# Schematic.net
KiCad netlist of a schematic drawn in EAGLE
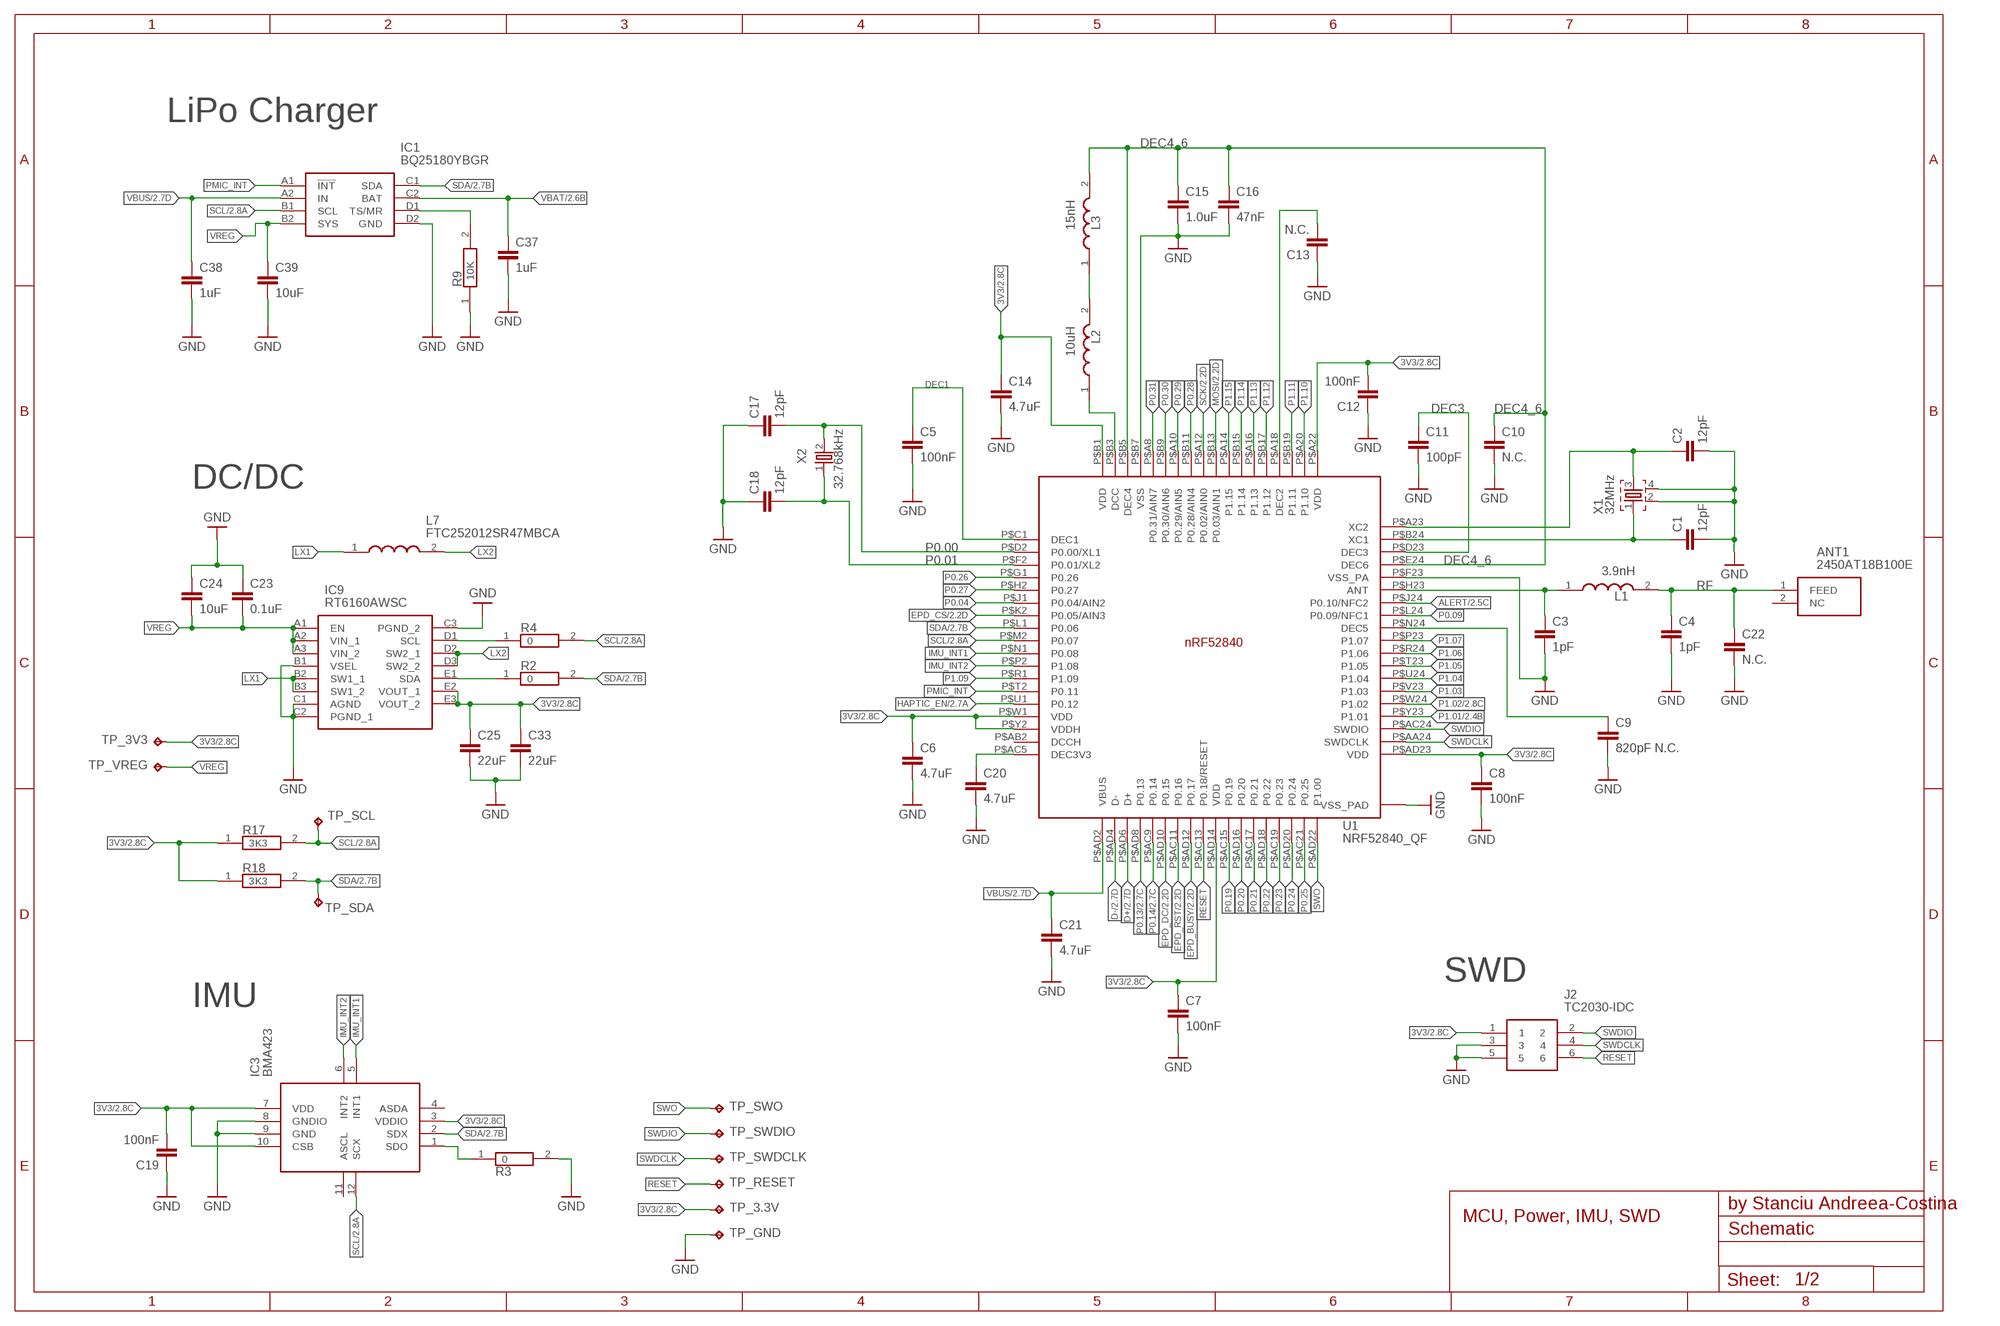
[diagram p0: schematic, sheet 1]
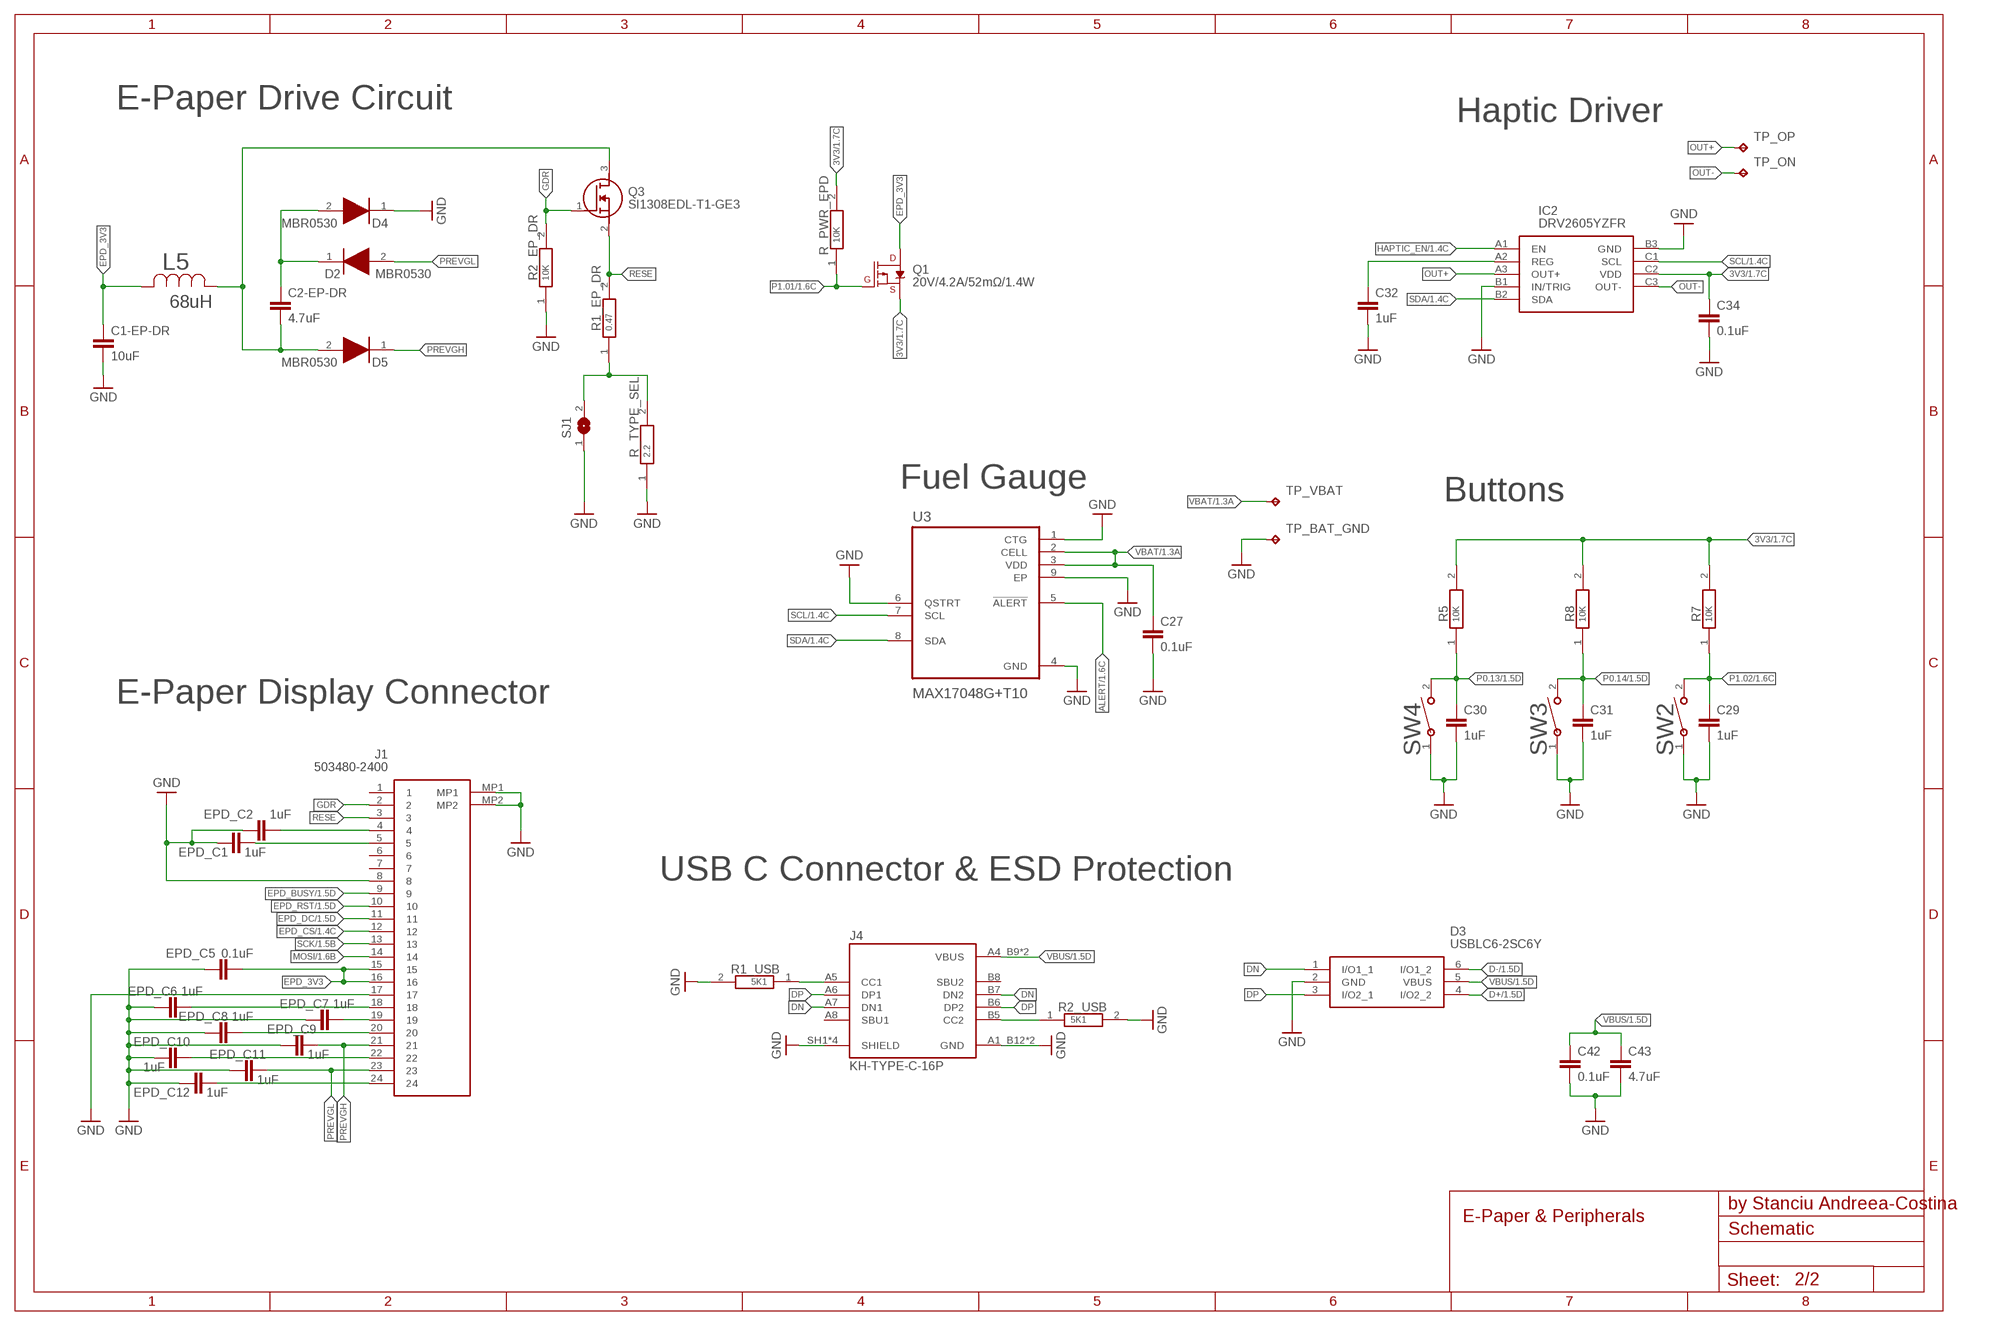
[diagram p1: schematic, sheet 2]

(export (version "E")
  (design (tool "Eeschema 10.0.6"))
  (components
    (comp (ref "ANT1")
      (value "2450AT18B100E")
      (footprint "eagle-import:2450AT18B100E_ANTC3216X140N")
      (fields (field (name "MOUSER_PART_NUMBER") "609-2450AT18B100E"))
      (libsource (lib "eagle-import") (part "2450AT18B100E_2450AT18B100E"))
    )
    (comp (ref "C1")
      (value "12pF")
      (footprint "eagle-import:NORDIC_NRF_3_RESC0201_N")
      (libsource (lib "eagle-import") (part "InkTime_v5_vf.H3x0luehSd-qGlYKXrjHOA_NORDIC_NRF_3_CAPACITOR_0201_N"))
    )
    (comp (ref "C2")
      (value "12pF")
      (footprint "eagle-import:NORDIC_NRF_3_RESC0201_N")
      (libsource (lib "eagle-import") (part "InkTime_v5_vf.H3x0luehSd-qGlYKXrjHOA_NORDIC_NRF_3_CAPACITOR_0201_N"))
    )
    (comp (ref "C3")
      (value "1pF")
      (footprint "eagle-import:NORDIC_NRF_3_RESC0201_N")
      (libsource (lib "eagle-import") (part "InkTime_v5_vf.H3x0luehSd-qGlYKXrjHOA_NORDIC_NRF_3_CAPACITOR_0201_N"))
    )
    (comp (ref "C4")
      (value "1pF")
      (footprint "eagle-import:NORDIC_NRF_3_RESC0201_N")
      (libsource (lib "eagle-import") (part "InkTime_v5_vf.H3x0luehSd-qGlYKXrjHOA_NORDIC_NRF_3_CAPACITOR_0201_N"))
    )
    (comp (ref "C5")
      (value "100nF")
      (footprint "eagle-import:NORDIC_NRF_3_RESC0201_N")
      (libsource (lib "eagle-import") (part "InkTime_v5_vf.H3x0luehSd-qGlYKXrjHOA_NORDIC_NRF_3_CAPACITOR_0201_N"))
    )
    (comp (ref "C6")
      (value "4.7uF")
      (footprint "eagle-import:NORDIC_NRF_3_RESC0402_N")
      (libsource (lib "eagle-import") (part "InkTime_v5_vf.H3x0luehSd-qGlYKXrjHOA_NORDIC_NRF_3_CAPACITOR_0402_N"))
    )
    (comp (ref "C7")
      (value "100nF")
      (footprint "eagle-import:NORDIC_NRF_3_RESC0201_N")
      (libsource (lib "eagle-import") (part "InkTime_v5_vf.H3x0luehSd-qGlYKXrjHOA_NORDIC_NRF_3_CAPACITOR_0201_N"))
    )
    (comp (ref "C8")
      (value "100nF")
      (footprint "eagle-import:NORDIC_NRF_3_RESC0201_N")
      (libsource (lib "eagle-import") (part "InkTime_v5_vf.H3x0luehSd-qGlYKXrjHOA_NORDIC_NRF_3_CAPACITOR_0201_N"))
    )
    (comp (ref "C9")
      (value "820pF N.C.")
      (footprint "eagle-import:NORDIC_NRF_3_RESC0201_N")
      (libsource (lib "eagle-import") (part "InkTime_v5_vf.H3x0luehSd-qGlYKXrjHOA_NORDIC_NRF_3_CAPACITOR_0201_N"))
    )
    (comp (ref "C10")
      (value "N.C.")
      (footprint "eagle-import:NORDIC_NRF_3_RESC0201_N")
      (libsource (lib "eagle-import") (part "InkTime_v5_vf.H3x0luehSd-qGlYKXrjHOA_NORDIC_NRF_3_CAPACITOR_0201_N"))
    )
    (comp (ref "C11")
      (value "100pF")
      (footprint "eagle-import:NORDIC_NRF_3_RESC0201_N")
      (libsource (lib "eagle-import") (part "InkTime_v5_vf.H3x0luehSd-qGlYKXrjHOA_NORDIC_NRF_3_CAPACITOR_0201_N"))
    )
    (comp (ref "C12")
      (value "100nF")
      (footprint "eagle-import:NORDIC_NRF_3_RESC0201_N")
      (libsource (lib "eagle-import") (part "InkTime_v5_vf.H3x0luehSd-qGlYKXrjHOA_NORDIC_NRF_3_CAPACITOR_0201_N"))
    )
    (comp (ref "C13")
      (value "N.C.")
      (footprint "eagle-import:NORDIC_NRF_3_RESC0201_N")
      (libsource (lib "eagle-import") (part "InkTime_v5_vf.H3x0luehSd-qGlYKXrjHOA_NORDIC_NRF_3_CAPACITOR_0201_N"))
    )
    (comp (ref "C14")
      (value "4.7uF")
      (footprint "eagle-import:NORDIC_NRF_3_RESC0402_N")
      (libsource (lib "eagle-import") (part "InkTime_v5_vf.H3x0luehSd-qGlYKXrjHOA_NORDIC_NRF_3_CAPACITOR_0402_N"))
    )
    (comp (ref "C15")
      (value "1.0uF")
      (footprint "eagle-import:NORDIC_NRF_3_RESC0402_N")
      (libsource (lib "eagle-import") (part "InkTime_v5_vf.H3x0luehSd-qGlYKXrjHOA_NORDIC_NRF_3_CAPACITOR_0402_N"))
    )
    (comp (ref "C16")
      (value "47nF")
      (footprint "eagle-import:NORDIC_NRF_3_RESC0201_N")
      (libsource (lib "eagle-import") (part "InkTime_v5_vf.H3x0luehSd-qGlYKXrjHOA_NORDIC_NRF_3_CAPACITOR_0201_N"))
    )
    (comp (ref "C17")
      (value "12pF")
      (footprint "eagle-import:NORDIC_NRF_3_RESC0201_N")
      (libsource (lib "eagle-import") (part "InkTime_v5_vf.H3x0luehSd-qGlYKXrjHOA_NORDIC_NRF_3_CAPACITOR_0201_N"))
    )
    (comp (ref "C18")
      (value "12pF")
      (footprint "eagle-import:NORDIC_NRF_3_RESC0201_N")
      (libsource (lib "eagle-import") (part "InkTime_v5_vf.H3x0luehSd-qGlYKXrjHOA_NORDIC_NRF_3_CAPACITOR_0201_N"))
    )
    (comp (ref "C19")
      (value "100nF")
      (footprint "eagle-import:NORDIC_NRF_3_RESC0201_N")
      (libsource (lib "eagle-import") (part "InkTime_v5_vf.H3x0luehSd-qGlYKXrjHOA_NORDIC_NRF_3_CAPACITOR_0201_N"))
    )
    (comp (ref "C20")
      (value "4.7uF")
      (footprint "eagle-import:NORDIC_NRF_3_RESC0402_N")
      (libsource (lib "eagle-import") (part "InkTime_v5_vf.H3x0luehSd-qGlYKXrjHOA_NORDIC_NRF_3_CAPACITOR_0402_N"))
    )
    (comp (ref "C21")
      (value "4.7uF")
      (footprint "eagle-import:NORDIC_NRF_3_RESC0402_N")
      (libsource (lib "eagle-import") (part "InkTime_v5_vf.H3x0luehSd-qGlYKXrjHOA_NORDIC_NRF_3_CAPACITOR_0402_N"))
    )
    (comp (ref "C22")
      (value "N.C.")
      (footprint "eagle-import:NORDIC_NRF_3_RESC0201_N")
      (libsource (lib "eagle-import") (part "InkTime_v5_vf.H3x0luehSd-qGlYKXrjHOA_NORDIC_NRF_3_CAPACITOR_0201_N"))
    )
    (comp (ref "C23")
      (value "0.1uF")
      (footprint "eagle-import:NORDIC_NRF_3_RESC0201_N")
      (libsource (lib "eagle-import") (part "InkTime_v5_vf.H3x0luehSd-qGlYKXrjHOA_NORDIC_NRF_3_CAPACITOR_0201_N"))
    )
    (comp (ref "C24")
      (value "10uF")
      (footprint "eagle-import:NORDIC_NRF_3_RESC0402_N")
      (libsource (lib "eagle-import") (part "InkTime_v5_vf.H3x0luehSd-qGlYKXrjHOA_NORDIC_NRF_3_CAPACITOR_0402_N"))
    )
    (comp (ref "C25")
      (value "22uF")
      (footprint "eagle-import:NORDIC_NRF_3_RESC0402_N")
      (libsource (lib "eagle-import") (part "InkTime_v5_vf.H3x0luehSd-qGlYKXrjHOA_NORDIC_NRF_3_CAPACITOR_0402_N"))
    )
    (comp (ref "C33")
      (value "22uF")
      (footprint "eagle-import:NORDIC_NRF_3_RESC0402_N")
      (libsource (lib "eagle-import") (part "InkTime_v5_vf.H3x0luehSd-qGlYKXrjHOA_NORDIC_NRF_3_CAPACITOR_0402_N"))
    )
    (comp (ref "C37")
      (value "1uF")
      (footprint "eagle-import:NORDIC_NRF_3_RESC0402_N")
      (libsource (lib "eagle-import") (part "NORDIC_NRF_3_CAPACITOR_0402_N"))
    )
    (comp (ref "C38")
      (value "1uF")
      (footprint "eagle-import:NORDIC_NRF_3_RESC0402_N")
      (libsource (lib "eagle-import") (part "NORDIC_NRF_3_CAPACITOR_0402_N"))
    )
    (comp (ref "C39")
      (value "10uF")
      (footprint "eagle-import:NORDIC_NRF_3_RESC0402_N")
      (libsource (lib "eagle-import") (part "NORDIC_NRF_3_CAPACITOR_0402_N"))
    )
    (comp (ref "IC1")
      (value "BQ25180YBGR")
      (footprint "eagle-import:BQ25180YBGR_BGA8C40P2X4_100X155X50")
      (fields (field (name "MOUSER_PART_NUMBER") "595-BQ25180YBGR"))
      (libsource (lib "eagle-import") (part "BQ25180YBGR_BQ25180YBGR"))
    )
    (comp (ref "IC3")
      (value "BMA423")
      (footprint "eagle-import:BMA423_BMA423")
      (fields (field (name "MOUSER_PART_NUMBER") "262-BMA423"))
      (libsource (lib "eagle-import") (part "BMA423_BMA423"))
    )
    (comp (ref "IC9")
      (value "RT6160AWSC")
      (footprint "eagle-import:RT6160AWSC_BGA15C40P3X5_140X230X60")
      (fields (field (name "MOUSER_PART_NUMBER") "835-RT6160AWSC"))
      (libsource (lib "eagle-import") (part "RT6160AWSC_RT6160AWSC"))
    )
    (comp (ref "J2")
      (value "TC2030-IDC")
      (footprint "eagle-import:TC2030-IDC_TC2030IDC")
      (libsource (lib "eagle-import") (part "TC2030-IDC_TC2030-IDC"))
    )
    (comp (ref "L1")
      (value "3.9nH")
      (footprint "eagle-import:MLP2016SR47MT0S1_INDC2016X100N")
      (fields (field (name "MANUFACTURER_PART_NUMBER") "FTC252012SR47MBCA"))
      (libsource (lib "eagle-import") (part "MLP2016SR47MT0S1_FTC252012SR47MBCA"))
    )
    (comp (ref "L2")
      (value "10uH")
      (footprint "eagle-import:MLP2016SR47MT0S1_INDC2016X100N")
      (fields (field (name "MANUFACTURER_PART_NUMBER") "FTC252012SR47MBCA"))
      (libsource (lib "eagle-import") (part "MLP2016SR47MT0S1_FTC252012SR47MBCA"))
    )
    (comp (ref "L3")
      (value "15nH")
      (footprint "eagle-import:MLP2016SR47MT0S1_INDC2016X100N")
      (fields (field (name "MANUFACTURER_PART_NUMBER") "FTC252012SR47MBCA"))
      (libsource (lib "eagle-import") (part "MLP2016SR47MT0S1_FTC252012SR47MBCA"))
    )
    (comp (ref "L7")
      (value "FTC252012SR47MBCA")
      (footprint "eagle-import:MLP2016SR47MT0S1_INDC2016X100N")
      (libsource (lib "eagle-import") (part "MLP2016SR47MT0S1_FTC252012SR47MBCA"))
    )
    (comp (ref "R2")
      (value "0")
      (footprint "eagle-import:CPF0201D7K68C1_0201")
      (libsource (lib "eagle-import") (part "CPF0201D7K68C1_CPF0201D7K68C1"))
    )
    (comp (ref "R3")
      (value "0")
      (footprint "eagle-import:CPF0201D7K68C1_0201")
      (libsource (lib "eagle-import") (part "CPF0201D7K68C1_CPF0201D7K68C1"))
    )
    (comp (ref "R4")
      (value "0")
      (footprint "eagle-import:CPF0201D7K68C1_0201")
      (libsource (lib "eagle-import") (part "CPF0201D7K68C1_CPF0201D7K68C1"))
    )
    (comp (ref "R9")
      (value "10K")
      (footprint "eagle-import:CPF0201D7K68C1_0201")
      (libsource (lib "eagle-import") (part "CPF0201D7K68C1_CPF0201D7K68C1"))
    )
    (comp (ref "R17")
      (value "3K3")
      (footprint "eagle-import:CPF0201D7K68C1_0201")
      (libsource (lib "eagle-import") (part "CPF0201D7K68C1_CPF0201D7K68C1"))
    )
    (comp (ref "R18")
      (value "3K3")
      (footprint "eagle-import:CPF0201D7K68C1_0201")
      (libsource (lib "eagle-import") (part "CPF0201D7K68C1_CPF0201D7K68C1"))
    )
    (comp (ref "TP_3.3V")
      (value "HECTOR_WATCH_1_TPTP20R")
      (footprint "eagle-import:HECTOR_WATCH_1_TP20R")
      (libsource (lib "eagle-import") (part "HECTOR_WATCH_1_TPTP20R"))
    )
    (comp (ref "TP_3V3")
      (value "HECTOR_WATCH_1_TPTP20R")
      (footprint "eagle-import:HECTOR_WATCH_1_TP20R")
      (libsource (lib "eagle-import") (part "HECTOR_WATCH_1_TPTP20R"))
    )
    (comp (ref "TP_GND")
      (value "HECTOR_WATCH_1_TPTP20R")
      (footprint "eagle-import:HECTOR_WATCH_1_TP20R")
      (libsource (lib "eagle-import") (part "HECTOR_WATCH_1_TPTP20R"))
    )
    (comp (ref "TP_RESET")
      (value "HECTOR_WATCH_1_TPTP20R")
      (footprint "eagle-import:HECTOR_WATCH_1_TP20R")
      (libsource (lib "eagle-import") (part "HECTOR_WATCH_1_TPTP20R"))
    )
    (comp (ref "TP_SCL")
      (value "HECTOR_WATCH_1_TPTP20R")
      (footprint "eagle-import:HECTOR_WATCH_1_TP20R")
      (libsource (lib "eagle-import") (part "HECTOR_WATCH_1_TPTP20R"))
    )
    (comp (ref "TP_SDA")
      (value "HECTOR_WATCH_1_TPTP20R")
      (footprint "eagle-import:HECTOR_WATCH_1_TP20R")
      (libsource (lib "eagle-import") (part "HECTOR_WATCH_1_TPTP20R"))
    )
    (comp (ref "TP_SWDCLK")
      (value "HECTOR_WATCH_1_TPTP20R")
      (footprint "eagle-import:HECTOR_WATCH_1_TP20R")
      (libsource (lib "eagle-import") (part "HECTOR_WATCH_1_TPTP20R"))
    )
    (comp (ref "TP_SWDIO")
      (value "HECTOR_WATCH_1_TPTP20R")
      (footprint "eagle-import:HECTOR_WATCH_1_TP20R")
      (libsource (lib "eagle-import") (part "HECTOR_WATCH_1_TPTP20R"))
    )
    (comp (ref "TP_SWO")
      (value "HECTOR_WATCH_1_TPTP20R")
      (footprint "eagle-import:HECTOR_WATCH_1_TP20R")
      (libsource (lib "eagle-import") (part "HECTOR_WATCH_1_TPTP20R"))
    )
    (comp (ref "TP_VREG")
      (value "HECTOR_WATCH_1_TPTP20R")
      (footprint "eagle-import:HECTOR_WATCH_1_TP20R")
      (libsource (lib "eagle-import") (part "HECTOR_WATCH_1_TPTP20R"))
    )
    (comp (ref "U1")
      (value "NRF52840_QF")
      (footprint "eagle-import:NORDIC_NRF_4_AQFN50P700X700X85_HS-74N")
      (libsource (lib "eagle-import") (part "NORDIC_NRF_4_NRF52840_QF"))
    )
    (comp (ref "X1")
      (value "32MHz")
      (footprint "eagle-import:NORDIC_NRF_BT-XTAL_2016_N")
      (libsource (lib "eagle-import") (part "NORDIC_NRF_XTAL_32MHZ"))
    )
    (comp (ref "X2")
      (value "32.768kHz")
      (footprint "eagle-import:NORDIC_NRF_1_XTAL_3215_N")
      (libsource (lib "eagle-import") (part "NORDIC_NRF_1_XTAL_32KHZ"))
    )
    (comp (ref "C1-EP-DR")
      (value "10uF")
      (footprint "eagle-import:NORDIC_NRF_3_RESC0402_N")
      (libsource (lib "eagle-import") (part "InkTime_v5_vf.H3x0luehSd-qGlYKXrjHOA_NORDIC_NRF_3_CAPACITOR_0402_N"))
    )
    (comp (ref "C2-EP-DR")
      (value "4.7uF")
      (footprint "eagle-import:NORDIC_NRF_3_RESC0402_N")
      (libsource (lib "eagle-import") (part "InkTime_v5_vf.H3x0luehSd-qGlYKXrjHOA_NORDIC_NRF_3_CAPACITOR_0402_N"))
    )
    (comp (ref "C27")
      (value "0.1uF")
      (footprint "eagle-import:NORDIC_NRF_3_RESC0201_N")
      (libsource (lib "eagle-import") (part "InkTime_v5_vf.H3x0luehSd-qGlYKXrjHOA_NORDIC_NRF_3_CAPACITOR_0201_N"))
    )
    (comp (ref "C29")
      (value "1uF")
      (footprint "eagle-import:NORDIC_NRF_3_RESC0402_N")
      (libsource (lib "eagle-import") (part "InkTime_v5_vf.H3x0luehSd-qGlYKXrjHOA_NORDIC_NRF_3_CAPACITOR_0402_N"))
    )
    (comp (ref "C30")
      (value "1uF")
      (footprint "eagle-import:NORDIC_NRF_3_RESC0402_N")
      (libsource (lib "eagle-import") (part "InkTime_v5_vf.H3x0luehSd-qGlYKXrjHOA_NORDIC_NRF_3_CAPACITOR_0402_N"))
    )
    (comp (ref "C31")
      (value "1uF")
      (footprint "eagle-import:NORDIC_NRF_3_RESC0402_N")
      (libsource (lib "eagle-import") (part "InkTime_v5_vf.H3x0luehSd-qGlYKXrjHOA_NORDIC_NRF_3_CAPACITOR_0402_N"))
    )
    (comp (ref "C32")
      (value "1uF")
      (footprint "eagle-import:NORDIC_NRF_3_RESC0402_N")
      (libsource (lib "eagle-import") (part "InkTime_v5_vf.H3x0luehSd-qGlYKXrjHOA_NORDIC_NRF_3_CAPACITOR_0402_N"))
    )
    (comp (ref "C34")
      (value "0.1uF")
      (footprint "eagle-import:NORDIC_NRF_3_RESC0201_N")
      (libsource (lib "eagle-import") (part "InkTime_v5_vf.H3x0luehSd-qGlYKXrjHOA_NORDIC_NRF_3_CAPACITOR_0201_N"))
    )
    (comp (ref "C42")
      (value "0.1uF")
      (footprint "eagle-import:NORDIC_NRF_3_RESC0201_N")
      (libsource (lib "eagle-import") (part "InkTime_v5_vf.H3x0luehSd-qGlYKXrjHOA_NORDIC_NRF_3_CAPACITOR_0201_N"))
    )
    (comp (ref "C43")
      (value "4.7uF")
      (footprint "eagle-import:NORDIC_NRF_3_RESC0402_N")
      (libsource (lib "eagle-import") (part "InkTime_v5_vf.H3x0luehSd-qGlYKXrjHOA_NORDIC_NRF_3_CAPACITOR_0402_N"))
    )
    (comp (ref "D2")
      (value "MBR0530")
      (footprint "eagle-import:ESP32_C6_LIBRARY_5_SOD3716X135N")
      (fields (field (name "MF") "ON Semiconductor"))
      (libsource (lib "eagle-import") (part "ESP32_C6_LIBRARY_5_MBR0530"))
    )
    (comp (ref "D3")
      (value "USBLC6-2SC6Y")
      (footprint "eagle-import:ESP32_C6_LIBRARY_3_SOT95P280X145-6N")
      (fields (field (name "MF") "STMicroelectronics"))
      (libsource (lib "eagle-import") (part "ESP32_C6_LIBRARY_3_USBLC6-2SC6Y"))
    )
    (comp (ref "D4")
      (value "MBR0530")
      (footprint "eagle-import:ESP32_C6_LIBRARY_5_SOD3716X135N")
      (fields (field (name "MF") "ON Semiconductor"))
      (libsource (lib "eagle-import") (part "ESP32_C6_LIBRARY_5_MBR0530"))
    )
    (comp (ref "D5")
      (value "MBR0530")
      (footprint "eagle-import:ESP32_C6_LIBRARY_5_SOD3716X135N")
      (fields (field (name "MF") "ON Semiconductor"))
      (libsource (lib "eagle-import") (part "ESP32_C6_LIBRARY_5_MBR0530"))
    )
    (comp (ref "EPD_C1")
      (value "1uF")
      (footprint "eagle-import:NORDIC_NRF_3_RESC0402_N")
      (libsource (lib "eagle-import") (part "InkTime_v5_vf.H3x0luehSd-qGlYKXrjHOA_NORDIC_NRF_3_CAPACITOR_0402_N"))
    )
    (comp (ref "EPD_C2")
      (value "1uF")
      (footprint "eagle-import:NORDIC_NRF_3_RESC0402_N")
      (libsource (lib "eagle-import") (part "InkTime_v5_vf.H3x0luehSd-qGlYKXrjHOA_NORDIC_NRF_3_CAPACITOR_0402_N"))
    )
    (comp (ref "EPD_C5")
      (value "0.1uF")
      (footprint "eagle-import:NORDIC_NRF_3_RESC0201_N")
      (libsource (lib "eagle-import") (part "InkTime_v5_vf.H3x0luehSd-qGlYKXrjHOA_NORDIC_NRF_3_CAPACITOR_0201_N"))
    )
    (comp (ref "EPD_C6")
      (value "1uF")
      (footprint "eagle-import:NORDIC_NRF_3_RESC0402_N")
      (libsource (lib "eagle-import") (part "InkTime_v5_vf.H3x0luehSd-qGlYKXrjHOA_NORDIC_NRF_3_CAPACITOR_0402_N"))
    )
    (comp (ref "EPD_C7")
      (value "1uF")
      (footprint "eagle-import:NORDIC_NRF_3_RESC0402_N")
      (libsource (lib "eagle-import") (part "InkTime_v5_vf.H3x0luehSd-qGlYKXrjHOA_NORDIC_NRF_3_CAPACITOR_0402_N"))
    )
    (comp (ref "EPD_C8")
      (value "1uF")
      (footprint "eagle-import:NORDIC_NRF_3_RESC0402_N")
      (libsource (lib "eagle-import") (part "InkTime_v5_vf.H3x0luehSd-qGlYKXrjHOA_NORDIC_NRF_3_CAPACITOR_0402_N"))
    )
    (comp (ref "EPD_C9")
      (value "1uF")
      (footprint "eagle-import:NORDIC_NRF_3_RESC0402_N")
      (libsource (lib "eagle-import") (part "InkTime_v5_vf.H3x0luehSd-qGlYKXrjHOA_NORDIC_NRF_3_CAPACITOR_0402_N"))
    )
    (comp (ref "EPD_C10")
      (value "1uF")
      (footprint "eagle-import:NORDIC_NRF_3_RESC0402_N")
      (libsource (lib "eagle-import") (part "InkTime_v5_vf.H3x0luehSd-qGlYKXrjHOA_NORDIC_NRF_3_CAPACITOR_0402_N"))
    )
    (comp (ref "EPD_C11")
      (value "1uF")
      (footprint "eagle-import:NORDIC_NRF_3_RESC0402_N")
      (libsource (lib "eagle-import") (part "InkTime_v5_vf.H3x0luehSd-qGlYKXrjHOA_NORDIC_NRF_3_CAPACITOR_0402_N"))
    )
    (comp (ref "EPD_C12")
      (value "1uF")
      (footprint "eagle-import:NORDIC_NRF_3_RESC0402_N")
      (libsource (lib "eagle-import") (part "InkTime_v5_vf.H3x0luehSd-qGlYKXrjHOA_NORDIC_NRF_3_CAPACITOR_0402_N"))
    )
    (comp (ref "IC2")
      (value "DRV2605YZFR")
      (footprint "eagle-import:DRV2605YZFR_BGA9C50P3X3_144X144X62")
      (libsource (lib "eagle-import") (part "DRV2605YZFR_DRV2605YZFR"))
    )
    (comp (ref "J1")
      (value "503480-2400")
      (footprint "eagle-import:503480-2400_5034802400")
      (fields (field (name "MOUSER_PART_NUMBER") "538-503480-2400"))
      (libsource (lib "eagle-import") (part "503480-2400_503480-2400"))
    )
    (comp (ref "J4")
      (value "KH-TYPE-C-16P")
      (footprint "eagle-import:KH-TYPE-C-16P_KINGHELM_KH-TYPE-C-16P")
      (fields (field (name "MF") "kinghelm"))
      (libsource (lib "eagle-import") (part "KH-TYPE-C-16P_KH-TYPE-C-16P"))
    )
    (comp (ref "L5")
      (value "68uH")
      (footprint "eagle-import:ESP32_C6_LIBRARY_2_IND_4828-WE-TPC_WRE")
      (fields
        (field (name "MANUFACTURER_PART_NUMBER") "744043680")
        (field (name "COPYRIGHT") "Copyright (C) 2024 Ultra Librarian. All rights reserved.")
      )
      (libsource (lib "eagle-import") (part "ESP32_C6_LIBRARY_2_744043680IND_4828-WE-TPC_WRE"))
    )
    (comp (ref "Q1")
      (value "20V/4.2A/52mΩ/1.4W")
      (footprint "eagle-import:ESP32_C6_LIBRARY_4_ESP32_C6_LIBRARY_4_ESP32_C6_LIBRARY_4_ESP32_C6_LIBRARY_4_ESP32_WROVER_SPARKFUN-DISCRETESEMI_SOT23-3")
      (libsource (lib "eagle-import") (part "ESP32_C6_LIBRARY_4_ESP32_WROVER_SPARKFUN-DISCRETESEMI_MOSFET_PCH-DMG2305UX-7"))
    )
    (comp (ref "Q3")
      (value "SI1308EDL-T1-GE3")
      (footprint "eagle-import:ESP32_C6_LIBRARY_6_SOT65P210X110-3N")
      (fields (field (name "MF") "Vishay Siliconix"))
      (libsource (lib "eagle-import") (part "ESP32_C6_LIBRARY_6_SI1308EDL-T1-GE3"))
    )
    (comp (ref "R1_EP_DR")
      (value "0.47")
      (footprint "eagle-import:CPF0201D7K68C1_0201")
      (libsource (lib "eagle-import") (part "CPF0201D7K68C1_CPF0201D7K68C1"))
    )
    (comp (ref "R1_USB")
      (value "5K1")
      (footprint "eagle-import:CPF0201D7K68C1_0201")
      (libsource (lib "eagle-import") (part "CPF0201D7K68C1_CPF0201D7K68C1"))
    )
    (comp (ref "R2_EP_DR")
      (value "10K")
      (footprint "eagle-import:CPF0201D7K68C1_0201")
      (libsource (lib "eagle-import") (part "CPF0201D7K68C1_CPF0201D7K68C1"))
    )
    (comp (ref "R2_USB")
      (value "5K1")
      (footprint "eagle-import:CPF0201D7K68C1_0201")
      (libsource (lib "eagle-import") (part "CPF0201D7K68C1_CPF0201D7K68C1"))
    )
    (comp (ref "R5")
      (value "10K")
      (footprint "eagle-import:CPF0201D7K68C1_0201")
      (libsource (lib "eagle-import") (part "CPF0201D7K68C1_CPF0201D7K68C1"))
    )
    (comp (ref "R7")
      (value "10K")
      (footprint "eagle-import:CPF0201D7K68C1_0201")
      (libsource (lib "eagle-import") (part "CPF0201D7K68C1_CPF0201D7K68C1"))
    )
    (comp (ref "R8")
      (value "10K")
      (footprint "eagle-import:CPF0201D7K68C1_0201")
      (libsource (lib "eagle-import") (part "CPF0201D7K68C1_CPF0201D7K68C1"))
    )
    (comp (ref "R_PWR_EPD")
      (value "10K")
      (footprint "eagle-import:CPF0201D7K68C1_0201")
      (libsource (lib "eagle-import") (part "CPF0201D7K68C1_CPF0201D7K68C1"))
    )
    (comp (ref "R_TYPE_SEL")
      (value "2.2")
      (footprint "eagle-import:CPF0201D7K68C1_0201")
      (libsource (lib "eagle-import") (part "CPF0201D7K68C1_CPF0201D7K68C1"))
    )
    (comp (ref "SJ1")
      (value "ESP32_C6_LIBRARY_7_JUMPER_SJ")
      (footprint "eagle-import:ESP32_C6_LIBRARY_7_JUMPER_SJ")
      (libsource (lib "eagle-import") (part "ESP32_C6_LIBRARY_7_JUMPER_SJ"))
    )
    (comp (ref "SW2")
      (value "0")
      (footprint "eagle-import:2025-10-22_07-23-44_LIBRARY_SW_EVP-AKE31A_PAN")
      (fields
        (field (name "MANUFACTURER_PART_NUMBER") "EVP-AKE31A")
        (field (name "COPYRIGHT") "Copyright (C) 2025 Ultra Librarian. All rights reserved.")
      )
      (libsource (lib "eagle-import") (part "2025-10-22_07-23-44_LIBRARY_EVP-AKE31ASW_EVP-AKE31A_PAN"))
    )
    (comp (ref "SW3")
      (value "0")
      (footprint "eagle-import:2025-10-22_07-23-44_LIBRARY_SW_EVP-AKE31A_PAN")
      (fields
        (field (name "MANUFACTURER_PART_NUMBER") "EVP-AKE31A")
        (field (name "COPYRIGHT") "Copyright (C) 2025 Ultra Librarian. All rights reserved.")
      )
      (libsource (lib "eagle-import") (part "2025-10-22_07-23-44_LIBRARY_EVP-AKE31ASW_EVP-AKE31A_PAN"))
    )
    (comp (ref "SW4")
      (value "0")
      (footprint "eagle-import:2025-10-22_07-23-44_LIBRARY_SW_EVP-AKE31A_PAN")
      (fields
        (field (name "MANUFACTURER_PART_NUMBER") "EVP-AKE31A")
        (field (name "COPYRIGHT") "Copyright (C) 2025 Ultra Librarian. All rights reserved.")
      )
      (libsource (lib "eagle-import") (part "2025-10-22_07-23-44_LIBRARY_EVP-AKE31ASW_EVP-AKE31A_PAN"))
    )
    (comp (ref "TP_BAT_GND")
      (value "HECTOR_WATCH_1_TPTP20R")
      (footprint "eagle-import:HECTOR_WATCH_1_TP20R")
      (libsource (lib "eagle-import") (part "HECTOR_WATCH_1_TPTP20R"))
    )
    (comp (ref "TP_ON")
      (value "HECTOR_WATCH_1_TPTP20R")
      (footprint "eagle-import:HECTOR_WATCH_1_TP20R")
      (libsource (lib "eagle-import") (part "HECTOR_WATCH_1_TPTP20R"))
    )
    (comp (ref "TP_OP")
      (value "HECTOR_WATCH_1_TPTP20R")
      (footprint "eagle-import:HECTOR_WATCH_1_TP20R")
      (libsource (lib "eagle-import") (part "HECTOR_WATCH_1_TPTP20R"))
    )
    (comp (ref "TP_VBAT")
      (value "HECTOR_WATCH_1_TPTP20R")
      (footprint "eagle-import:HECTOR_WATCH_1_TP20R")
      (libsource (lib "eagle-import") (part "HECTOR_WATCH_1_TPTP20R"))
    )
    (comp (ref "U3")
      (value "MAX17048G+T10")
      (footprint "eagle-import:ESP32_C6_LIBRARY_SON50P200X200X80-9N")
      (fields (field (name "MF") "Analog Devices"))
      (libsource (lib "eagle-import") (part "ESP32_C6_LIBRARY_MAX17048G+T10"))
    )
  )
  (nets
    (net (code "1") (name "3V3") (class "Default")
      (node (ref "C12") (pin "2") (pinfunction "2_2") (pintype "passive"))
      (node (ref "C14") (pin "1") (pinfunction "1_1") (pintype "passive"))
      (node (ref "C19") (pin "2") (pinfunction "2_2") (pintype "passive"))
      (node (ref "C25") (pin "1") (pinfunction "1_1") (pintype "passive"))
      (node (ref "C33") (pin "1") (pinfunction "1_1") (pintype "passive"))
      (node (ref "C34") (pin "1") (pinfunction "1_1") (pintype "passive"))
      (node (ref "C6") (pin "1") (pinfunction "1_1") (pintype "passive"))
      (node (ref "C7") (pin "1") (pinfunction "1_1") (pintype "passive"))
      (node (ref "C8") (pin "1") (pinfunction "1_1") (pintype "passive"))
      (node (ref "IC2") (pin "C2") (pinfunction "VDD_C2") (pintype "bidirectional"))
      (node (ref "IC3") (pin "10") (pinfunction "CSB_10") (pintype "bidirectional"))
      (node (ref "IC3") (pin "3") (pinfunction "VDDIO_3") (pintype "bidirectional"))
      (node (ref "IC3") (pin "7") (pinfunction "VDD_7") (pintype "bidirectional"))
      (node (ref "IC9") (pin "E2") (pinfunction "VOUT_1_E2") (pintype "bidirectional"))
      (node (ref "IC9") (pin "E3") (pinfunction "VOUT_2_E3") (pintype "bidirectional"))
      (node (ref "J2") (pin "1") (pinfunction "1_1") (pintype "bidirectional"))
      (node (ref "Q1") (pin "2") (pinfunction "S_2") (pintype "bidirectional"))
      (node (ref "R17") (pin "1") (pinfunction "1_1") (pintype "bidirectional"))
      (node (ref "R18") (pin "1") (pinfunction "1_1") (pintype "bidirectional"))
      (node (ref "R5") (pin "2") (pinfunction "2_2") (pintype "bidirectional"))
      (node (ref "R7") (pin "2") (pinfunction "2_2") (pintype "bidirectional"))
      (node (ref "R8") (pin "2") (pinfunction "2_2") (pintype "bidirectional"))
      (node (ref "R_PWR_EPD") (pin "2") (pinfunction "2_2") (pintype "bidirectional"))
      (node (ref "TP_3.3V") (pin "TP") (pinfunction "TP_TP") (pintype "input"))
      (node (ref "TP_3V3") (pin "TP") (pinfunction "TP_TP") (pintype "input"))
      (node (ref "U1") (pin "P$A22") (pinfunction "VDD_P$A22") (pintype "power_in"))
      (node (ref "U1") (pin "P$AD14") (pinfunction "VDD_P$AD14") (pintype "power_in"))
      (node (ref "U1") (pin "P$AD23") (pinfunction "VDD_P$AD23") (pintype "power_in"))
      (node (ref "U1") (pin "P$B1") (pinfunction "VDD_P$B1") (pintype "power_in"))
      (node (ref "U1") (pin "P$W1") (pinfunction "VDD_P$W1") (pintype "power_in"))
      (node (ref "U1") (pin "P$Y2") (pinfunction "VDDH_P$Y2") (pintype "power_in"))
    )
    (net (code "2") (name "ALERT") (class "Default")
      (node (ref "U1") (pin "P$J24") (pinfunction "P0.10/NFC2_P$J24") (pintype "bidirectional"))
      (node (ref "U3") (pin "5") (pinfunction "~{ALERT}_5") (pintype "output"))
    )
    (net (code "3") (name "D+") (class "Default")
      (node (ref "D3") (pin "4") (pinfunction "I/O2_2_4") (pintype "bidirectional"))
      (node (ref "U1") (pin "P$AD6") (pinfunction "D+_P$AD6") (pintype "bidirectional"))
    )
    (net (code "4") (name "D-") (class "Default")
      (node (ref "D3") (pin "6") (pinfunction "I/O1_2_6") (pintype "bidirectional"))
      (node (ref "U1") (pin "P$AD4") (pinfunction "D-_P$AD4") (pintype "bidirectional"))
    )
    (net (code "5") (name "DEC1") (class "Default")
      (node (ref "C5") (pin "1") (pinfunction "1_1") (pintype "passive"))
      (node (ref "U1") (pin "P$C1") (pinfunction "DEC1_P$C1") (pintype "power_in"))
    )
    (net (code "6") (name "DEC3") (class "Default")
      (node (ref "C11") (pin "1") (pinfunction "1_1") (pintype "passive"))
      (node (ref "U1") (pin "P$D23") (pinfunction "DEC3_P$D23") (pintype "bidirectional"))
    )
    (net (code "7") (name "DEC4_6") (class "Default")
      (node (ref "C10") (pin "1") (pinfunction "1_1") (pintype "passive"))
      (node (ref "C15") (pin "1") (pinfunction "1_1") (pintype "passive"))
      (node (ref "C16") (pin "1") (pinfunction "1_1") (pintype "passive"))
      (node (ref "L3") (pin "2") (pinfunction "2_2") (pintype "bidirectional"))
      (node (ref "U1") (pin "P$B5") (pinfunction "DEC4_P$B5") (pintype "power_in"))
      (node (ref "U1") (pin "P$E24") (pinfunction "DEC6_P$E24") (pintype "bidirectional"))
    )
    (net (code "8") (name "DN") (class "Default")
      (node (ref "D3") (pin "1") (pinfunction "I/O1_1_1") (pintype "bidirectional"))
      (node (ref "J4") (pin "A7") (pinfunction "DN1_A7") (pintype "bidirectional"))
      (node (ref "J4") (pin "B7") (pinfunction "DN2_B7") (pintype "bidirectional"))
    )
    (net (code "9") (name "DP") (class "Default")
      (node (ref "D3") (pin "3") (pinfunction "I/O2_1_3") (pintype "bidirectional"))
      (node (ref "J4") (pin "A6") (pinfunction "DP1_A6") (pintype "bidirectional"))
      (node (ref "J4") (pin "B6") (pinfunction "DP2_B6") (pintype "bidirectional"))
    )
    (net (code "10") (name "EPD_3V3") (class "Default")
      (node (ref "C1-EP-DR") (pin "1") (pinfunction "1_1") (pintype "passive"))
      (node (ref "EPD_C5") (pin "2") (pinfunction "2_2") (pintype "passive"))
      (node (ref "J1") (pin "15") (pinfunction "15_15") (pintype "bidirectional"))
      (node (ref "J1") (pin "16") (pinfunction "16_16") (pintype "bidirectional"))
      (node (ref "L5") (pin "2") (pinfunction "2_2") (pintype "passive"))
      (node (ref "Q1") (pin "3") (pinfunction "D_3") (pintype "bidirectional"))
    )
    (net (code "11") (name "EPD_BUSY") (class "Default")
      (node (ref "J1") (pin "9") (pinfunction "9_9") (pintype "bidirectional"))
      (node (ref "U1") (pin "P$AD12") (pinfunction "P0.17_P$AD12") (pintype "bidirectional"))
    )
    (net (code "12") (name "EPD_CS") (class "Default")
      (node (ref "J1") (pin "12") (pinfunction "12_12") (pintype "bidirectional"))
      (node (ref "U1") (pin "P$K2") (pinfunction "P0.05/AIN3_P$K2") (pintype "bidirectional"))
    )
    (net (code "13") (name "EPD_DC") (class "Default")
      (node (ref "J1") (pin "11") (pinfunction "11_11") (pintype "bidirectional"))
      (node (ref "U1") (pin "P$AD10") (pinfunction "P0.15_P$AD10") (pintype "bidirectional"))
    )
    (net (code "14") (name "EPD_RST") (class "Default")
      (node (ref "J1") (pin "10") (pinfunction "10_10") (pintype "bidirectional"))
      (node (ref "U1") (pin "P$AC11") (pinfunction "P0.16_P$AC11") (pintype "bidirectional"))
    )
    (net (code "15") (name "GDR") (class "Default")
      (node (ref "J1") (pin "2") (pinfunction "2_2") (pintype "bidirectional"))
      (node (ref "Q3") (pin "1") (pinfunction "G_1") (pintype "bidirectional"))
      (node (ref "R2_EP_DR") (pin "2") (pinfunction "2_2") (pintype "bidirectional"))
    )
    (net (code "16") (name "GND") (class "Default")
      (node (ref "C1") (pin "2") (pinfunction "2_2") (pintype "passive"))
      (node (ref "C1-EP-DR") (pin "2") (pinfunction "2_2") (pintype "passive"))
      (node (ref "C10") (pin "2") (pinfunction "2_2") (pintype "passive"))
      (node (ref "C11") (pin "2") (pinfunction "2_2") (pintype "passive"))
      (node (ref "C12") (pin "1") (pinfunction "1_1") (pintype "passive"))
      (node (ref "C13") (pin "1") (pinfunction "1_1") (pintype "passive"))
      (node (ref "C14") (pin "2") (pinfunction "2_2") (pintype "passive"))
      (node (ref "C15") (pin "2") (pinfunction "2_2") (pintype "passive"))
      (node (ref "C16") (pin "2") (pinfunction "2_2") (pintype "passive"))
      (node (ref "C17") (pin "1") (pinfunction "1_1") (pintype "passive"))
      (node (ref "C18") (pin "1") (pinfunction "1_1") (pintype "passive"))
      (node (ref "C19") (pin "1") (pinfunction "1_1") (pintype "passive"))
      (node (ref "C2") (pin "2") (pinfunction "2_2") (pintype "passive"))
      (node (ref "C20") (pin "2") (pinfunction "2_2") (pintype "passive"))
      (node (ref "C21") (pin "2") (pinfunction "2_2") (pintype "passive"))
      (node (ref "C22") (pin "2") (pinfunction "2_2") (pintype "passive"))
      (node (ref "C23") (pin "1") (pinfunction "1_1") (pintype "passive"))
      (node (ref "C24") (pin "1") (pinfunction "1_1") (pintype "passive"))
      (node (ref "C25") (pin "2") (pinfunction "2_2") (pintype "passive"))
      (node (ref "C27") (pin "2") (pinfunction "2_2") (pintype "passive"))
      (node (ref "C29") (pin "2") (pinfunction "2_2") (pintype "passive"))
      (node (ref "C3") (pin "2") (pinfunction "2_2") (pintype "passive"))
      (node (ref "C30") (pin "2") (pinfunction "2_2") (pintype "passive"))
      (node (ref "C31") (pin "2") (pinfunction "2_2") (pintype "passive"))
      (node (ref "C32") (pin "2") (pinfunction "2_2") (pintype "passive"))
      (node (ref "C33") (pin "2") (pinfunction "2_2") (pintype "passive"))
      (node (ref "C34") (pin "2") (pinfunction "2_2") (pintype "passive"))
      (node (ref "C37") (pin "2") (pinfunction "2_2") (pintype "passive"))
      (node (ref "C38") (pin "2") (pinfunction "2_2") (pintype "passive"))
      (node (ref "C39") (pin "2") (pinfunction "2_2") (pintype "passive"))
      (node (ref "C4") (pin "2") (pinfunction "2_2") (pintype "passive"))
      (node (ref "C42") (pin "2") (pinfunction "2_2") (pintype "passive"))
      (node (ref "C43") (pin "2") (pinfunction "2_2") (pintype "passive"))
      (node (ref "C5") (pin "2") (pinfunction "2_2") (pintype "passive"))
      (node (ref "C6") (pin "2") (pinfunction "2_2") (pintype "passive"))
      (node (ref "C7") (pin "2") (pinfunction "2_2") (pintype "passive"))
      (node (ref "C8") (pin "2") (pinfunction "2_2") (pintype "passive"))
      (node (ref "C9") (pin "2") (pinfunction "2_2") (pintype "passive"))
      (node (ref "D3") (pin "2") (pinfunction "GND_2") (pintype "bidirectional"))
      (node (ref "D4") (pin "1") (pinfunction "K_1") (pintype "bidirectional"))
      (node (ref "EPD_C1") (pin "1") (pinfunction "1_1") (pintype "passive"))
      (node (ref "EPD_C10") (pin "1") (pinfunction "1_1") (pintype "passive"))
      (node (ref "EPD_C11") (pin "1") (pinfunction "1_1") (pintype "passive"))
      (node (ref "EPD_C12") (pin "1") (pinfunction "1_1") (pintype "passive"))
      (node (ref "EPD_C2") (pin "1") (pinfunction "1_1") (pintype "passive"))
      (node (ref "EPD_C5") (pin "1") (pinfunction "1_1") (pintype "passive"))
      (node (ref "EPD_C6") (pin "1") (pinfunction "1_1") (pintype "passive"))
      (node (ref "EPD_C7") (pin "1") (pinfunction "1_1") (pintype "passive"))
      (node (ref "EPD_C8") (pin "1") (pinfunction "1_1") (pintype "passive"))
      (node (ref "EPD_C9") (pin "1") (pinfunction "1_1") (pintype "passive"))
      (node (ref "IC1") (pin "D2") (pinfunction "GND_D2") (pintype "bidirectional"))
      (node (ref "IC2") (pin "B1") (pinfunction "IN/TRIG_B1") (pintype "bidirectional"))
      (node (ref "IC2") (pin "B3") (pinfunction "GND_B3") (pintype "bidirectional"))
      (node (ref "IC3") (pin "8") (pinfunction "GNDIO_8") (pintype "bidirectional"))
      (node (ref "IC3") (pin "9") (pinfunction "GND_9") (pintype "bidirectional"))
      (node (ref "IC9") (pin "B1") (pinfunction "VSEL_B1") (pintype "bidirectional"))
      (node (ref "IC9") (pin "C1") (pinfunction "AGND_C1") (pintype "bidirectional"))
      (node (ref "IC9") (pin "C2") (pinfunction "PGND_1_C2") (pintype "bidirectional"))
      (node (ref "IC9") (pin "C3") (pinfunction "PGND_2_C3") (pintype "bidirectional"))
      (node (ref "J1") (pin "17") (pinfunction "17_17") (pintype "bidirectional"))
      (node (ref "J1") (pin "8") (pinfunction "8_8") (pintype "bidirectional"))
      (node (ref "J1") (pin "MP1") (pinfunction "MP1_MP1") (pintype "bidirectional"))
      (node (ref "J1") (pin "MP2") (pinfunction "MP2_MP2") (pintype "bidirectional"))
      (node (ref "J2") (pin "3") (pinfunction "3_3") (pintype "bidirectional"))
      (node (ref "J2") (pin "5") (pinfunction "5_5") (pintype "bidirectional"))
      (node (ref "J4") (pin "A12_B1") (pinfunction "GND_A12_B1") (pintype "power_in"))
      (node (ref "J4") (pin "A1_B12") (pinfunction "GND_A1_B12") (pintype "power_in"))
      (node (ref "J4") (pin "SH1") (pinfunction "SHIELD_SH1") (pintype "passive"))
      (node (ref "J4") (pin "SH2") (pinfunction "SHIELD_SH2") (pintype "passive"))
      (node (ref "J4") (pin "SH3") (pinfunction "SHIELD_SH3") (pintype "passive"))
      (node (ref "J4") (pin "SH4") (pinfunction "SHIELD_SH4") (pintype "passive"))
      (node (ref "R1_USB") (pin "2") (pinfunction "2_2") (pintype "bidirectional"))
      (node (ref "R2_EP_DR") (pin "1") (pinfunction "1_1") (pintype "bidirectional"))
      (node (ref "R2_USB") (pin "2") (pinfunction "2_2") (pintype "bidirectional"))
      (node (ref "R3") (pin "2") (pinfunction "2_2") (pintype "bidirectional"))
      (node (ref "R9") (pin "1") (pinfunction "1_1") (pintype "bidirectional"))
      (node (ref "R_TYPE_SEL") (pin "1") (pinfunction "1_1") (pintype "bidirectional"))
      (node (ref "SJ1") (pin "1") (pinfunction "1_1") (pintype "passive"))
      (node (ref "SW2") (pin "1") (pinfunction "1_1") (pintype "passive"))
      (node (ref "SW3") (pin "1") (pinfunction "1_1") (pintype "passive"))
      (node (ref "SW4") (pin "1") (pinfunction "1_1") (pintype "passive"))
      (node (ref "TP_BAT_GND") (pin "TP") (pinfunction "TP_TP") (pintype "input"))
      (node (ref "TP_GND") (pin "TP") (pinfunction "TP_TP") (pintype "input"))
      (node (ref "U1") (pin "P$74") (pinfunction "VSS_PAD_P$74") (pintype "bidirectional"))
      (node (ref "U1") (pin "P$75") (pinfunction "VSS_PAD_P$75") (pintype "bidirectional"))
      (node (ref "U1") (pin "P$76") (pinfunction "VSS_PAD_P$76") (pintype "bidirectional"))
      (node (ref "U1") (pin "P$77") (pinfunction "VSS_PAD_P$77") (pintype "bidirectional"))
      (node (ref "U1") (pin "P$78") (pinfunction "VSS_PAD_P$78") (pintype "bidirectional"))
      (node (ref "U1") (pin "P$79") (pinfunction "VSS_PAD_P$79") (pintype "bidirectional"))
      (node (ref "U1") (pin "P$80") (pinfunction "VSS_PAD_P$80") (pintype "bidirectional"))
      (node (ref "U1") (pin "P$81") (pinfunction "VSS_PAD_P$81") (pintype "bidirectional"))
      (node (ref "U1") (pin "P$82") (pinfunction "VSS_PAD_P$82") (pintype "bidirectional"))
      (node (ref "U1") (pin "P$83") (pinfunction "VSS_PAD_P$83") (pintype "bidirectional"))
      (node (ref "U1") (pin "P$84") (pinfunction "VSS_PAD_P$84") (pintype "bidirectional"))
      (node (ref "U1") (pin "P$85") (pinfunction "VSS_PAD_P$85") (pintype "bidirectional"))
      (node (ref "U1") (pin "P$86") (pinfunction "VSS_PAD_P$86") (pintype "bidirectional"))
      (node (ref "U1") (pin "P$87") (pinfunction "VSS_PAD_P$87") (pintype "bidirectional"))
      (node (ref "U1") (pin "P$88") (pinfunction "VSS_PAD_P$88") (pintype "bidirectional"))
      (node (ref "U1") (pin "P$89") (pinfunction "VSS_PAD_P$89") (pintype "bidirectional"))
      (node (ref "U1") (pin "P$90") (pinfunction "VSS_PAD_P$90") (pintype "bidirectional"))
      (node (ref "U1") (pin "P$B7") (pinfunction "VSS_P$B7") (pintype "power_in"))
      (node (ref "U1") (pin "P$F23") (pinfunction "VSS_PA_P$F23") (pintype "bidirectional"))
      (node (ref "U3") (pin "1") (pinfunction "CTG_1") (pintype "power_in"))
      (node (ref "U3") (pin "4") (pinfunction "GND_4") (pintype "power_in"))
      (node (ref "U3") (pin "6") (pinfunction "QSTRT_6") (pintype "input"))
      (node (ref "U3") (pin "9") (pinfunction "EP_9") (pintype "power_in"))
      (node (ref "X1") (pin "2") (pinfunction "2_2") (pintype "passive"))
      (node (ref "X1") (pin "4") (pinfunction "4_4") (pintype "passive"))
    )
    (net (code "17") (name "HAPTIC_EN") (class "Default")
      (node (ref "IC2") (pin "A1") (pinfunction "EN_A1") (pintype "bidirectional"))
      (node (ref "U1") (pin "P$U1") (pinfunction "P0.12_P$U1") (pintype "bidirectional"))
    )
    (net (code "18") (name "IMU_INT1") (class "Default")
      (node (ref "IC3") (pin "5") (pinfunction "INT1_5") (pintype "bidirectional"))
      (node (ref "U1") (pin "P$N1") (pinfunction "P0.08_P$N1") (pintype "bidirectional"))
    )
    (net (code "19") (name "IMU_INT2") (class "Default")
      (node (ref "IC3") (pin "6") (pinfunction "INT2_6") (pintype "bidirectional"))
      (node (ref "U1") (pin "P$P2") (pinfunction "P1.08_P$P2") (pintype "bidirectional"))
    )
    (net (code "20") (name "LX1") (class "Default")
      (node (ref "IC9") (pin "B2") (pinfunction "SW1_1_B2") (pintype "bidirectional"))
      (node (ref "IC9") (pin "B3") (pinfunction "SW1_2_B3") (pintype "bidirectional"))
      (node (ref "L7") (pin "1") (pinfunction "1_1") (pintype "bidirectional"))
    )
    (net (code "21") (name "LX2") (class "Default")
      (node (ref "IC9") (pin "D2") (pinfunction "SW2_1_D2") (pintype "bidirectional"))
      (node (ref "IC9") (pin "D3") (pinfunction "SW2_2_D3") (pintype "bidirectional"))
      (node (ref "L7") (pin "2") (pinfunction "2_2") (pintype "bidirectional"))
    )
    (net (code "22") (name "MOSI") (class "Default")
      (node (ref "J1") (pin "14") (pinfunction "14_14") (pintype "bidirectional"))
      (node (ref "U1") (pin "P$B13") (pinfunction "P0.03/AIN1_P$B13") (pintype "bidirectional"))
    )
    (net (code "23") (name "Net-(D2-K)") (class "Default")
      (node (ref "C2-EP-DR") (pin "1") (pinfunction "1_1") (pintype "passive"))
      (node (ref "D2") (pin "1") (pinfunction "K_1") (pintype "bidirectional"))
      (node (ref "D4") (pin "2") (pinfunction "A_2") (pintype "bidirectional"))
    )
    (net (code "24") (name "Net-(D5-A)") (class "Default")
      (node (ref "C2-EP-DR") (pin "2") (pinfunction "2_2") (pintype "passive"))
      (node (ref "D5") (pin "2") (pinfunction "A_2") (pintype "bidirectional"))
      (node (ref "L5") (pin "1") (pinfunction "1_1") (pintype "passive"))
      (node (ref "Q3") (pin "3") (pinfunction "D_3") (pintype "bidirectional"))
    )
    (net (code "25") (name "Net-(EPD_C1-Pad2)") (class "Default")
      (node (ref "EPD_C1") (pin "2") (pinfunction "2_2") (pintype "passive"))
      (node (ref "J1") (pin "5") (pinfunction "5_5") (pintype "bidirectional"))
    )
    (net (code "26") (name "Net-(EPD_C2-Pad2)") (class "Default")
      (node (ref "EPD_C2") (pin "2") (pinfunction "2_2") (pintype "passive"))
      (node (ref "J1") (pin "4") (pinfunction "4_4") (pintype "bidirectional"))
    )
    (net (code "27") (name "Net-(EPD_C6-Pad2)") (class "Default")
      (node (ref "EPD_C6") (pin "2") (pinfunction "2_2") (pintype "passive"))
      (node (ref "J1") (pin "18") (pinfunction "18_18") (pintype "bidirectional"))
    )
    (net (code "28") (name "Net-(EPD_C7-Pad2)") (class "Default")
      (node (ref "EPD_C7") (pin "2") (pinfunction "2_2") (pintype "passive"))
      (node (ref "J1") (pin "19") (pinfunction "19_19") (pintype "bidirectional"))
    )
    (net (code "29") (name "Net-(EPD_C8-Pad2)") (class "Default")
      (node (ref "EPD_C8") (pin "2") (pinfunction "2_2") (pintype "passive"))
      (node (ref "J1") (pin "20") (pinfunction "20_20") (pintype "bidirectional"))
    )
    (net (code "30") (name "Net-(EPD_C10-Pad2)") (class "Default")
      (node (ref "EPD_C10") (pin "2") (pinfunction "2_2") (pintype "passive"))
      (node (ref "J1") (pin "22") (pinfunction "22_22") (pintype "bidirectional"))
    )
    (net (code "31") (name "Net-(EPD_C12-Pad2)") (class "Default")
      (node (ref "EPD_C12") (pin "2") (pinfunction "2_2") (pintype "passive"))
      (node (ref "J1") (pin "24") (pinfunction "24_24") (pintype "bidirectional"))
    )
    (net (code "32") (name "Net-(IC1-TS{slash}MR)") (class "Default")
      (node (ref "IC1") (pin "D1") (pinfunction "TS/MR_D1") (pintype "bidirectional"))
      (node (ref "R9") (pin "2") (pinfunction "2_2") (pintype "bidirectional"))
    )
    (net (code "33") (name "Net-(IC2-REG)") (class "Default")
      (node (ref "C32") (pin "1") (pinfunction "1_1") (pintype "passive"))
      (node (ref "IC2") (pin "A2") (pinfunction "REG_A2") (pintype "bidirectional"))
    )
    (net (code "34") (name "Net-(IC3-SDO)") (class "Default")
      (node (ref "IC3") (pin "1") (pinfunction "SDO_1") (pintype "bidirectional"))
      (node (ref "R3") (pin "1") (pinfunction "1_1") (pintype "bidirectional"))
    )
    (net (code "35") (name "Net-(IC9-SCL)") (class "Default")
      (node (ref "IC9") (pin "D1") (pinfunction "SCL_D1") (pintype "bidirectional"))
      (node (ref "R4") (pin "1") (pinfunction "1_1") (pintype "bidirectional"))
    )
    (net (code "36") (name "Net-(IC9-SDA)") (class "Default")
      (node (ref "IC9") (pin "E1") (pinfunction "SDA_E1") (pintype "bidirectional"))
      (node (ref "R2") (pin "1") (pinfunction "1_1") (pintype "bidirectional"))
    )
    (net (code "37") (name "Net-(J4-CC1)") (class "Default")
      (node (ref "J4") (pin "A5") (pinfunction "CC1_A5") (pintype "bidirectional"))
      (node (ref "R1_USB") (pin "1") (pinfunction "1_1") (pintype "bidirectional"))
    )
    (net (code "38") (name "Net-(J4-CC2)") (class "Default")
      (node (ref "J4") (pin "B5") (pinfunction "CC2_B5") (pintype "bidirectional"))
      (node (ref "R2_USB") (pin "1") (pinfunction "1_1") (pintype "bidirectional"))
    )
    (net (code "39") (name "Net-(L2-Pad2)") (class "Default")
      (node (ref "L2") (pin "2") (pinfunction "2_2") (pintype "bidirectional"))
      (node (ref "L3") (pin "1") (pinfunction "1_1") (pintype "bidirectional"))
    )
    (net (code "40") (name "Net-(R1_EP_DR-Pad1)") (class "Default")
      (node (ref "R1_EP_DR") (pin "1") (pinfunction "1_1") (pintype "bidirectional"))
      (node (ref "R_TYPE_SEL") (pin "2") (pinfunction "2_2") (pintype "bidirectional"))
      (node (ref "SJ1") (pin "2") (pinfunction "2_2") (pintype "passive"))
    )
    (net (code "41") (name "Net-(U1-ANT)") (class "Default")
      (node (ref "C3") (pin "1") (pinfunction "1_1") (pintype "passive"))
      (node (ref "L1") (pin "1") (pinfunction "1_1") (pintype "bidirectional"))
      (node (ref "U1") (pin "P$H23") (pinfunction "ANT_P$H23") (pintype "bidirectional"))
    )
    (net (code "42") (name "Net-(U1-DCC)") (class "Default")
      (node (ref "L2") (pin "1") (pinfunction "1_1") (pintype "bidirectional"))
      (node (ref "U1") (pin "P$B3") (pinfunction "DCC_P$B3") (pintype "output"))
    )
    (net (code "43") (name "Net-(U1-DEC2)") (class "Default")
      (node (ref "C13") (pin "2") (pinfunction "2_2") (pintype "passive"))
      (node (ref "U1") (pin "P$A18") (pinfunction "DEC2_P$A18") (pintype "bidirectional"))
    )
    (net (code "44") (name "Net-(U1-DEC3V3)") (class "Default")
      (node (ref "C20") (pin "1") (pinfunction "1_1") (pintype "passive"))
      (node (ref "U1") (pin "P$AC5") (pinfunction "DEC3V3_P$AC5") (pintype "bidirectional"))
    )
    (net (code "45") (name "Net-(U1-DEC5)") (class "Default")
      (node (ref "C9") (pin "1") (pinfunction "1_1") (pintype "passive"))
      (node (ref "U1") (pin "P$N24") (pinfunction "DEC5_P$N24") (pintype "bidirectional"))
    )
    (net (code "46") (name "Net-(U1-XC1)") (class "Default")
      (node (ref "C1") (pin "1") (pinfunction "1_1") (pintype "passive"))
      (node (ref "U1") (pin "P$B24") (pinfunction "XC1_P$B24") (pintype "input"))
      (node (ref "X1") (pin "1") (pinfunction "1_1") (pintype "passive"))
    )
    (net (code "47") (name "Net-(U1-XC2)") (class "Default")
      (node (ref "C2") (pin "1") (pinfunction "1_1") (pintype "passive"))
      (node (ref "U1") (pin "P$A23") (pinfunction "XC2_P$A23") (pintype "output"))
      (node (ref "X1") (pin "3") (pinfunction "3_3") (pintype "passive"))
    )
    (net (code "48") (name "OUT+") (class "Default")
      (node (ref "IC2") (pin "A3") (pinfunction "OUT+_A3") (pintype "bidirectional"))
      (node (ref "TP_OP") (pin "TP") (pinfunction "TP_TP") (pintype "input"))
    )
    (net (code "49") (name "OUT-") (class "Default")
      (node (ref "IC2") (pin "C3") (pinfunction "OUT-_C3") (pintype "bidirectional"))
      (node (ref "TP_ON") (pin "TP") (pinfunction "TP_TP") (pintype "input"))
    )
    (net (code "50") (name "P0.00") (class "Default")
      (node (ref "C17") (pin "2") (pinfunction "2_2") (pintype "passive"))
      (node (ref "U1") (pin "P$D2") (pinfunction "P0.00/XL1_P$D2") (pintype "bidirectional"))
      (node (ref "X2") (pin "2") (pinfunction "2_2") (pintype "passive"))
    )
    (net (code "51") (name "P0.01") (class "Default")
      (node (ref "C18") (pin "2") (pinfunction "2_2") (pintype "passive"))
      (node (ref "U1") (pin "P$F2") (pinfunction "P0.01/XL2_P$F2") (pintype "bidirectional"))
      (node (ref "X2") (pin "1") (pinfunction "1_1") (pintype "passive"))
    )
    (net (code "52") (name "P0.04") (class "Default")
      (node (ref "U1") (pin "P$J1") (pinfunction "P0.04/AIN2_P$J1") (pintype "bidirectional"))
    )
    (net (code "53") (name "P0.09") (class "Default")
      (node (ref "U1") (pin "P$L24") (pinfunction "P0.09/NFC1_P$L24") (pintype "bidirectional"))
    )
    (net (code "54") (name "P0.13") (class "Default")
      (node (ref "C30") (pin "1") (pinfunction "1_1") (pintype "passive"))
      (node (ref "R5") (pin "1") (pinfunction "1_1") (pintype "bidirectional"))
      (node (ref "SW4") (pin "2") (pinfunction "2_2") (pintype "passive"))
      (node (ref "U1") (pin "P$AD8") (pinfunction "P0.13_P$AD8") (pintype "bidirectional"))
    )
    (net (code "55") (name "P0.14") (class "Default")
      (node (ref "C31") (pin "1") (pinfunction "1_1") (pintype "passive"))
      (node (ref "R8") (pin "1") (pinfunction "1_1") (pintype "bidirectional"))
      (node (ref "SW3") (pin "2") (pinfunction "2_2") (pintype "passive"))
      (node (ref "U1") (pin "P$AC9") (pinfunction "P0.14_P$AC9") (pintype "bidirectional"))
    )
    (net (code "56") (name "P0.19") (class "Default")
      (node (ref "U1") (pin "P$AC15") (pinfunction "P0.19_P$AC15") (pintype "bidirectional"))
    )
    (net (code "57") (name "P0.20") (class "Default")
      (node (ref "U1") (pin "P$AD16") (pinfunction "P0.20_P$AD16") (pintype "bidirectional"))
    )
    (net (code "58") (name "P0.21") (class "Default")
      (node (ref "U1") (pin "P$AC17") (pinfunction "P0.21_P$AC17") (pintype "bidirectional"))
    )
    (net (code "59") (name "P0.22") (class "Default")
      (node (ref "U1") (pin "P$AD18") (pinfunction "P0.22_P$AD18") (pintype "bidirectional"))
    )
    (net (code "60") (name "P0.23") (class "Default")
      (node (ref "U1") (pin "P$AC19") (pinfunction "P0.23_P$AC19") (pintype "bidirectional"))
    )
    (net (code "61") (name "P0.24") (class "Default")
      (node (ref "U1") (pin "P$AD20") (pinfunction "P0.24_P$AD20") (pintype "bidirectional"))
    )
    (net (code "62") (name "P0.25") (class "Default")
      (node (ref "U1") (pin "P$AC21") (pinfunction "P0.25_P$AC21") (pintype "bidirectional"))
    )
    (net (code "63") (name "P0.26") (class "Default")
      (node (ref "U1") (pin "P$G1") (pinfunction "P0.26_P$G1") (pintype "bidirectional"))
    )
    (net (code "64") (name "P0.27") (class "Default")
      (node (ref "U1") (pin "P$H2") (pinfunction "P0.27_P$H2") (pintype "bidirectional"))
    )
    (net (code "65") (name "P0.28") (class "Default")
      (node (ref "U1") (pin "P$B11") (pinfunction "P0.28/AIN4_P$B11") (pintype "bidirectional"))
    )
    (net (code "66") (name "P0.29") (class "Default")
      (node (ref "U1") (pin "P$A10") (pinfunction "P0.29/AIN5_P$A10") (pintype "bidirectional"))
    )
    (net (code "67") (name "P0.30") (class "Default")
      (node (ref "U1") (pin "P$B9") (pinfunction "P0.30/AIN6_P$B9") (pintype "bidirectional"))
    )
    (net (code "68") (name "P0.31") (class "Default")
      (node (ref "U1") (pin "P$A8") (pinfunction "P0.31/AIN7_P$A8") (pintype "bidirectional"))
    )
    (net (code "69") (name "P1.01") (class "Default")
      (node (ref "Q1") (pin "1") (pinfunction "G_1") (pintype "bidirectional"))
      (node (ref "R_PWR_EPD") (pin "1") (pinfunction "1_1") (pintype "bidirectional"))
      (node (ref "U1") (pin "P$Y23") (pinfunction "P1.01_P$Y23") (pintype "bidirectional"))
    )
    (net (code "70") (name "P1.02") (class "Default")
      (node (ref "C29") (pin "1") (pinfunction "1_1") (pintype "passive"))
      (node (ref "R7") (pin "1") (pinfunction "1_1") (pintype "bidirectional"))
      (node (ref "SW2") (pin "2") (pinfunction "2_2") (pintype "passive"))
      (node (ref "U1") (pin "P$W24") (pinfunction "P1.02_P$W24") (pintype "bidirectional"))
    )
    (net (code "71") (name "P1.03") (class "Default")
      (node (ref "U1") (pin "P$V23") (pinfunction "P1.03_P$V23") (pintype "bidirectional"))
    )
    (net (code "72") (name "P1.04") (class "Default")
      (node (ref "U1") (pin "P$U24") (pinfunction "P1.04_P$U24") (pintype "bidirectional"))
    )
    (net (code "73") (name "P1.05") (class "Default")
      (node (ref "U1") (pin "P$T23") (pinfunction "P1.05_P$T23") (pintype "bidirectional"))
    )
    (net (code "74") (name "P1.06") (class "Default")
      (node (ref "U1") (pin "P$R24") (pinfunction "P1.06_P$R24") (pintype "bidirectional"))
    )
    (net (code "75") (name "P1.07") (class "Default")
      (node (ref "U1") (pin "P$P23") (pinfunction "P1.07_P$P23") (pintype "bidirectional"))
    )
    (net (code "76") (name "P1.09") (class "Default")
      (node (ref "U1") (pin "P$R1") (pinfunction "P1.09_P$R1") (pintype "bidirectional"))
    )
    (net (code "77") (name "P1.10") (class "Default")
      (node (ref "U1") (pin "P$A20") (pinfunction "P1.10_P$A20") (pintype "bidirectional"))
    )
    (net (code "78") (name "P1.11") (class "Default")
      (node (ref "U1") (pin "P$B19") (pinfunction "P1.11_P$B19") (pintype "bidirectional"))
    )
    (net (code "79") (name "P1.12") (class "Default")
      (node (ref "U1") (pin "P$B17") (pinfunction "P1.12_P$B17") (pintype "bidirectional"))
    )
    (net (code "80") (name "P1.13") (class "Default")
      (node (ref "U1") (pin "P$A16") (pinfunction "P1.13_P$A16") (pintype "bidirectional"))
    )
    (net (code "81") (name "P1.14") (class "Default")
      (node (ref "U1") (pin "P$B15") (pinfunction "P1.14_P$B15") (pintype "bidirectional"))
    )
    (net (code "82") (name "P1.15") (class "Default")
      (node (ref "U1") (pin "P$A14") (pinfunction "P1.15_P$A14") (pintype "bidirectional"))
    )
    (net (code "83") (name "PMIC_INT") (class "Default")
      (node (ref "IC1") (pin "A1") (pinfunction "~{INT}_A1") (pintype "bidirectional"))
      (node (ref "U1") (pin "P$T2") (pinfunction "P0.11_P$T2") (pintype "bidirectional"))
    )
    (net (code "84") (name "PREVGH") (class "Default")
      (node (ref "D5") (pin "1") (pinfunction "K_1") (pintype "bidirectional"))
      (node (ref "EPD_C9") (pin "2") (pinfunction "2_2") (pintype "passive"))
      (node (ref "J1") (pin "21") (pinfunction "21_21") (pintype "bidirectional"))
    )
    (net (code "85") (name "PREVGL") (class "Default")
      (node (ref "D2") (pin "2") (pinfunction "A_2") (pintype "bidirectional"))
      (node (ref "EPD_C11") (pin "2") (pinfunction "2_2") (pintype "passive"))
      (node (ref "J1") (pin "23") (pinfunction "23_23") (pintype "bidirectional"))
    )
    (net (code "86") (name "RESE") (class "Default")
      (node (ref "J1") (pin "3") (pinfunction "3_3") (pintype "bidirectional"))
      (node (ref "Q3") (pin "2") (pinfunction "S_2") (pintype "bidirectional"))
      (node (ref "R1_EP_DR") (pin "2") (pinfunction "2_2") (pintype "bidirectional"))
    )
    (net (code "87") (name "RESET") (class "Default")
      (node (ref "J2") (pin "6") (pinfunction "6_6") (pintype "bidirectional"))
      (node (ref "TP_RESET") (pin "TP") (pinfunction "TP_TP") (pintype "input"))
      (node (ref "U1") (pin "P$AC13") (pinfunction "P0.18/RESET_P$AC13") (pintype "bidirectional"))
    )
    (net (code "88") (name "RF") (class "Default")
      (node (ref "ANT1") (pin "1") (pinfunction "FEED_1") (pintype "input"))
      (node (ref "C22") (pin "1") (pinfunction "1_1") (pintype "passive"))
      (node (ref "C4") (pin "1") (pinfunction "1_1") (pintype "passive"))
      (node (ref "L1") (pin "2") (pinfunction "2_2") (pintype "bidirectional"))
    )
    (net (code "89") (name "SCK") (class "Default")
      (node (ref "J1") (pin "13") (pinfunction "13_13") (pintype "bidirectional"))
      (node (ref "U1") (pin "P$A12") (pinfunction "P0.02/AIN0_P$A12") (pintype "bidirectional"))
    )
    (net (code "90") (name "SCL") (class "Default")
      (node (ref "IC1") (pin "B1") (pinfunction "SCL_B1") (pintype "bidirectional"))
      (node (ref "IC2") (pin "C1") (pinfunction "SCL_C1") (pintype "bidirectional"))
      (node (ref "IC3") (pin "12") (pinfunction "SCX_12") (pintype "bidirectional"))
      (node (ref "R17") (pin "2") (pinfunction "2_2") (pintype "bidirectional"))
      (node (ref "R4") (pin "2") (pinfunction "2_2") (pintype "bidirectional"))
      (node (ref "TP_SCL") (pin "TP") (pinfunction "TP_TP") (pintype "input"))
      (node (ref "U1") (pin "P$M2") (pinfunction "P0.07_P$M2") (pintype "bidirectional"))
      (node (ref "U3") (pin "7") (pinfunction "SCL_7") (pintype "input"))
    )
    (net (code "91") (name "SDA") (class "Default")
      (node (ref "IC1") (pin "C1") (pinfunction "SDA_C1") (pintype "bidirectional"))
      (node (ref "IC2") (pin "B2") (pinfunction "SDA_B2") (pintype "bidirectional"))
      (node (ref "IC3") (pin "2") (pinfunction "SDX_2") (pintype "bidirectional"))
      (node (ref "R18") (pin "2") (pinfunction "2_2") (pintype "bidirectional"))
      (node (ref "R2") (pin "2") (pinfunction "2_2") (pintype "bidirectional"))
      (node (ref "TP_SDA") (pin "TP") (pinfunction "TP_TP") (pintype "input"))
      (node (ref "U1") (pin "P$L1") (pinfunction "P0.06_P$L1") (pintype "bidirectional"))
      (node (ref "U3") (pin "8") (pinfunction "SDA_8") (pintype "bidirectional"))
    )
    (net (code "92") (name "SWDCLK") (class "Default")
      (node (ref "J2") (pin "4") (pinfunction "4_4") (pintype "bidirectional"))
      (node (ref "TP_SWDCLK") (pin "TP") (pinfunction "TP_TP") (pintype "input"))
      (node (ref "U1") (pin "P$AA24") (pinfunction "SWDCLK_P$AA24") (pintype "input"))
    )
    (net (code "93") (name "SWDIO") (class "Default")
      (node (ref "J2") (pin "2") (pinfunction "2_2") (pintype "bidirectional"))
      (node (ref "TP_SWDIO") (pin "TP") (pinfunction "TP_TP") (pintype "input"))
      (node (ref "U1") (pin "P$AC24") (pinfunction "SWDIO_P$AC24") (pintype "bidirectional"))
    )
    (net (code "94") (name "SWO") (class "Default")
      (node (ref "TP_SWO") (pin "TP") (pinfunction "TP_TP") (pintype "input"))
      (node (ref "U1") (pin "P$AD22") (pinfunction "P1.00_P$AD22") (pintype "bidirectional"))
    )
    (net (code "95") (name "VBAT") (class "Default")
      (node (ref "C27") (pin "1") (pinfunction "1_1") (pintype "passive"))
      (node (ref "C37") (pin "1") (pinfunction "1_1") (pintype "passive"))
      (node (ref "IC1") (pin "C2") (pinfunction "BAT_C2") (pintype "bidirectional"))
      (node (ref "TP_VBAT") (pin "TP") (pinfunction "TP_TP") (pintype "input"))
      (node (ref "U3") (pin "2") (pinfunction "CELL_2") (pintype "power_in"))
      (node (ref "U3") (pin "3") (pinfunction "VDD_3") (pintype "power_in"))
    )
    (net (code "96") (name "VBUS") (class "Default")
      (node (ref "C21") (pin "1") (pinfunction "1_1") (pintype "passive"))
      (node (ref "C38") (pin "1") (pinfunction "1_1") (pintype "passive"))
      (node (ref "C42") (pin "1") (pinfunction "1_1") (pintype "passive"))
      (node (ref "C43") (pin "1") (pinfunction "1_1") (pintype "passive"))
      (node (ref "D3") (pin "5") (pinfunction "VBUS_5") (pintype "bidirectional"))
      (node (ref "IC1") (pin "A2") (pinfunction "IN_A2") (pintype "bidirectional"))
      (node (ref "J4") (pin "A4_B9") (pinfunction "VBUS_A4_B9") (pintype "power_in"))
      (node (ref "J4") (pin "A9_B4") (pinfunction "VBUS_A9_B4") (pintype "power_in"))
      (node (ref "U1") (pin "P$AD2") (pinfunction "VBUS_P$AD2") (pintype "power_in"))
    )
    (net (code "97") (name "VREG") (class "Default")
      (node (ref "C23") (pin "2") (pinfunction "2_2") (pintype "passive"))
      (node (ref "C24") (pin "2") (pinfunction "2_2") (pintype "passive"))
      (node (ref "C39") (pin "1") (pinfunction "1_1") (pintype "passive"))
      (node (ref "IC1") (pin "B2") (pinfunction "SYS_B2") (pintype "bidirectional"))
      (node (ref "IC9") (pin "A1") (pinfunction "EN_A1") (pintype "bidirectional"))
      (node (ref "IC9") (pin "A2") (pinfunction "VIN_1_A2") (pintype "bidirectional"))
      (node (ref "IC9") (pin "A3") (pinfunction "VIN_2_A3") (pintype "bidirectional"))
      (node (ref "TP_VREG") (pin "TP") (pinfunction "TP_TP") (pintype "input"))
    )
    (net (code "98") (name "unconnected-(ANT1-NC-Pad2)") (class "Default")
      (node (ref "ANT1") (pin "2") (pinfunction "NC_2") (pintype "no_connect"))
    )
    (net (code "99") (name "unconnected-(IC3-ASCL-Pad11)") (class "Default")
      (node (ref "IC3") (pin "11") (pinfunction "ASCL_11") (pintype "bidirectional"))
    )
    (net (code "100") (name "unconnected-(IC3-ASDA-Pad4)") (class "Default")
      (node (ref "IC3") (pin "4") (pinfunction "ASDA_4") (pintype "bidirectional"))
    )
    (net (code "101") (name "unconnected-(J1-Pad1)") (class "Default")
      (node (ref "J1") (pin "1") (pinfunction "1_1") (pintype "bidirectional"))
    )
    (net (code "102") (name "unconnected-(J1-Pad6)") (class "Default")
      (node (ref "J1") (pin "6") (pinfunction "6_6") (pintype "bidirectional"))
    )
    (net (code "103") (name "unconnected-(J1-Pad7)") (class "Default")
      (node (ref "J1") (pin "7") (pinfunction "7_7") (pintype "bidirectional"))
    )
    (net (code "104") (name "unconnected-(J4-SBU1-PadA8)") (class "Default")
      (node (ref "J4") (pin "A8") (pinfunction "SBU1_A8") (pintype "bidirectional"))
    )
    (net (code "105") (name "unconnected-(J4-SBU2-PadB8)") (class "Default")
      (node (ref "J4") (pin "B8") (pinfunction "SBU2_B8") (pintype "bidirectional"))
    )
    (net (code "106") (name "unconnected-(U1-DCCH-PadP$AB2)") (class "Default")
      (node (ref "U1") (pin "P$AB2") (pinfunction "DCCH_P$AB2") (pintype "bidirectional"))
    )
  )
)
